# RNG_entropy.net
KiCad netlist of a schematic drawn in Altium Designer
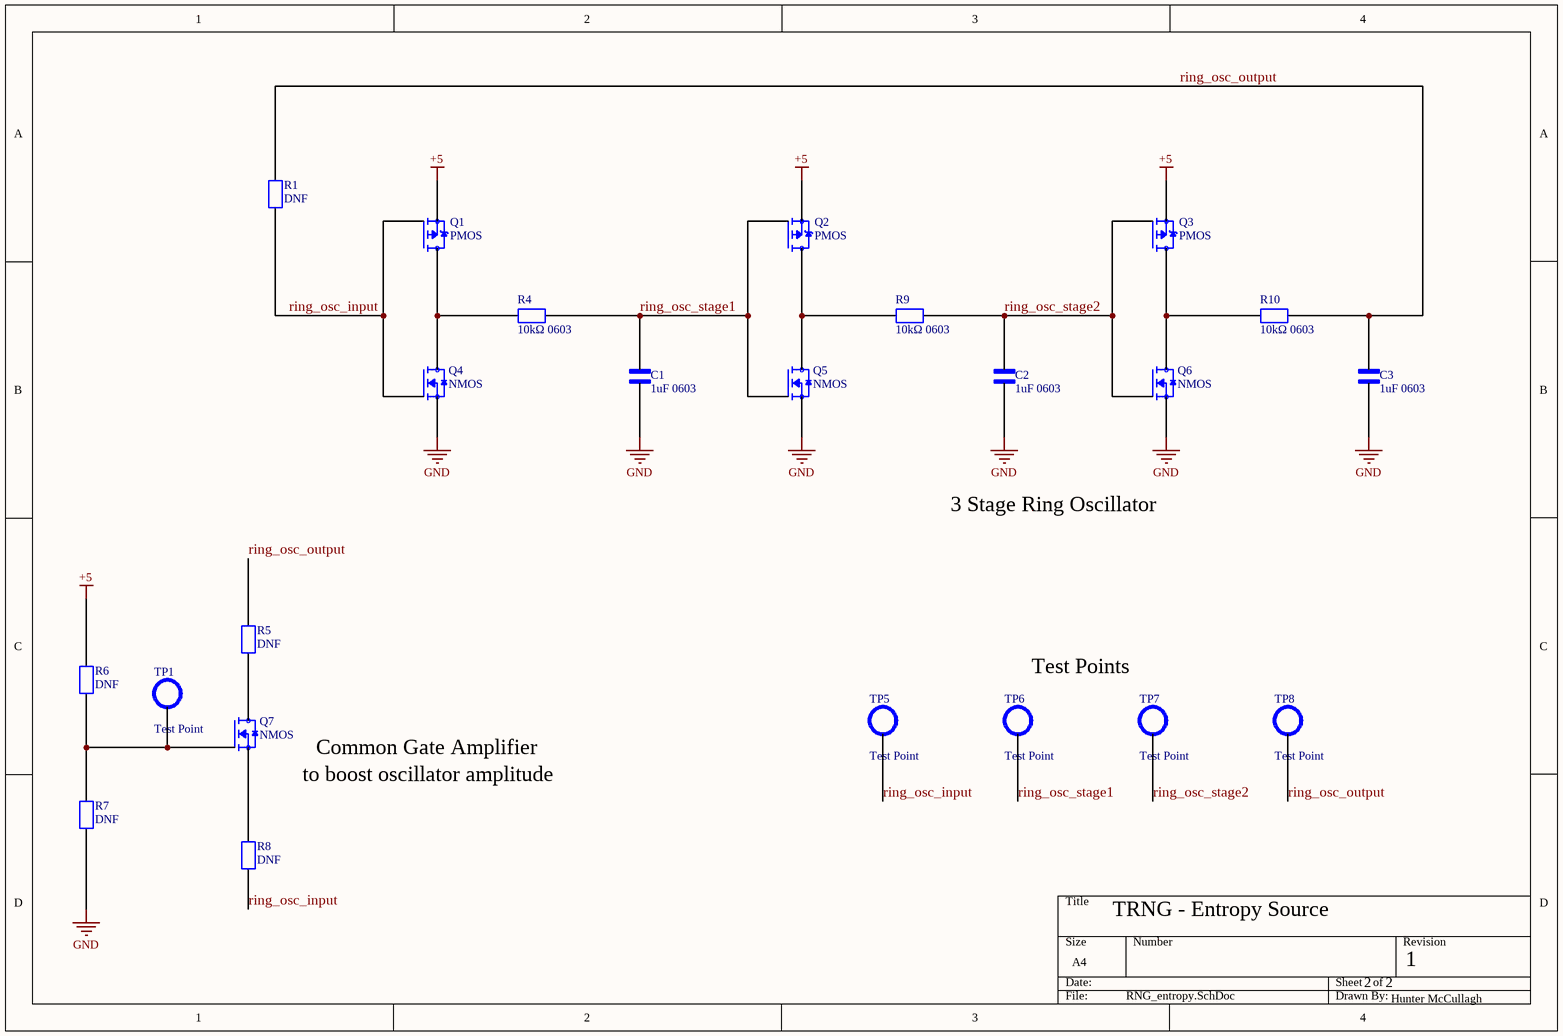
[diagram p0: RNG_entropy.SchDoc]

(export (version "E")
  (design (tool "Eeschema 10.0.6"))
  (components
    (comp (ref "C1")
      (value "1uF 0603")
      (footprint "0603 PACKAGE")
      (libsource (lib "RNG_schematic_lib") (part "0603_Capacitor"))
    )
    (comp (ref "C2")
      (value "1uF 0603")
      (footprint "0603 PACKAGE")
      (libsource (lib "RNG_schematic_lib") (part "0603_Capacitor"))
    )
    (comp (ref "C3")
      (value "1uF 0603")
      (footprint "0603 PACKAGE")
      (libsource (lib "RNG_schematic_lib") (part "0603_Capacitor"))
    )
    (comp (ref "Q1")
      (value "PMOS")
      (footprint "SOT23-3")
      (description "P-Channel 30 V 4A (Ta) 1.4W (Ta) Surface Mount SOT-23-3")
      (fields (field (name "MF") "Alpha & Omega Semiconductor") (field (name "MP") "AO3401A"))
      (libsource (lib "RNG_schematic_lib") (part "AO3401A"))
    )
    (comp (ref "Q2")
      (value "PMOS")
      (footprint "SOT23-3")
      (description "P-Channel 30 V 4A (Ta) 1.4W (Ta) Surface Mount SOT-23-3")
      (fields (field (name "MF") "Alpha & Omega Semiconductor") (field (name "MP") "AO3401A"))
      (libsource (lib "RNG_schematic_lib") (part "AO3401A"))
    )
    (comp (ref "Q3")
      (value "PMOS")
      (footprint "SOT23-3")
      (description "P-Channel 30 V 4A (Ta) 1.4W (Ta) Surface Mount SOT-23-3")
      (fields (field (name "MF") "Alpha & Omega Semiconductor") (field (name "MP") "AO3401A"))
      (libsource (lib "RNG_schematic_lib") (part "AO3401A"))
    )
    (comp (ref "Q4")
      (value "NMOS")
      (footprint "SOT23-3")
      (description "N-Channel 30 V 5.7A (Ta) 1.4W (Ta) Surface Mount SOT-23-3")
      (fields (field (name "MF") "Alpha & Omega Semiconductor") (field (name "MP") "AO3400A"))
      (libsource (lib "RNG_schematic_lib") (part "AO3400A"))
    )
    (comp (ref "Q5")
      (value "NMOS")
      (footprint "SOT23-3")
      (description "N-Channel 30 V 5.7A (Ta) 1.4W (Ta) Surface Mount SOT-23-3")
      (fields (field (name "MF") "Alpha & Omega Semiconductor") (field (name "MP") "AO3400A"))
      (libsource (lib "RNG_schematic_lib") (part "AO3400A"))
    )
    (comp (ref "Q6")
      (value "NMOS")
      (footprint "SOT23-3")
      (description "N-Channel 30 V 5.7A (Ta) 1.4W (Ta) Surface Mount SOT-23-3")
      (fields (field (name "MF") "Alpha & Omega Semiconductor") (field (name "MP") "AO3400A"))
      (libsource (lib "RNG_schematic_lib") (part "AO3400A"))
    )
    (comp (ref "Q7")
      (value "NMOS")
      (footprint "SOT23-3")
      (description "N-Channel 30 V 5.7A (Ta) 1.4W (Ta) Surface Mount SOT-23-3")
      (fields (field (name "MF") "Alpha & Omega Semiconductor") (field (name "MP") "AO3400A"))
      (libsource (lib "RNG_schematic_lib") (part "AO3400A"))
    )
    (comp (ref "R1")
      (value "DNF")
      (footprint "0402 PACKAGE")
      (libsource (lib "RNG_schematic_lib") (part "0402_Resistor"))
    )
    (comp (ref "R4")
      (value "10kΩ 0603")
      (footprint "0603 PACKAGE")
      (libsource (lib "RNG_schematic_lib") (part "0603_Resistor"))
    )
    (comp (ref "R5")
      (value "DNF")
      (footprint "0402 PACKAGE")
      (libsource (lib "RNG_schematic_lib") (part "0402_Resistor"))
    )
    (comp (ref "R6")
      (value "DNF")
      (footprint "0603 PACKAGE")
      (libsource (lib "RNG_schematic_lib") (part "0603_Resistor"))
    )
    (comp (ref "R7")
      (value "DNF")
      (footprint "0603 PACKAGE")
      (libsource (lib "RNG_schematic_lib") (part "0603_Resistor"))
    )
    (comp (ref "R8")
      (value "DNF")
      (footprint "0402 PACKAGE")
      (libsource (lib "RNG_schematic_lib") (part "0402_Resistor"))
    )
    (comp (ref "R9")
      (value "10kΩ 0603")
      (footprint "0603 PACKAGE")
      (libsource (lib "RNG_schematic_lib") (part "0603_Resistor"))
    )
    (comp (ref "R10")
      (value "10kΩ 0603")
      (footprint "0603 PACKAGE")
      (libsource (lib "RNG_schematic_lib") (part "0603_Resistor"))
    )
    (comp (ref "TP1")
      (value "Test Point")
      (footprint "Test Point")
      (libsource (lib "RNG_schematic_lib") (part "Test Point"))
    )
    (comp (ref "TP5")
      (value "Test Point")
      (footprint "Test Point")
      (libsource (lib "RNG_schematic_lib") (part "Test Point"))
    )
    (comp (ref "TP6")
      (value "Test Point")
      (footprint "Test Point")
      (libsource (lib "RNG_schematic_lib") (part "Test Point"))
    )
    (comp (ref "TP7")
      (value "Test Point")
      (footprint "Test Point")
      (libsource (lib "RNG_schematic_lib") (part "Test Point"))
    )
    (comp (ref "TP8")
      (value "Test Point")
      (footprint "Test Point")
      (libsource (lib "RNG_schematic_lib") (part "Test Point"))
    )
  )
  (nets
    (net (code "1") (name "+5") (class "Default")
      (node (ref "Q1") (pin "2") (pinfunction "S_2") (pintype "passive"))
      (node (ref "Q2") (pin "2") (pinfunction "S_2") (pintype "passive"))
      (node (ref "Q3") (pin "2") (pinfunction "S_2") (pintype "passive"))
      (node (ref "R6") (pin "2") (pinfunction "2_2") (pintype "passive"))
    )
    (net (code "2") (name "/ring_osc_input") (class "Default")
      (node (ref "Q1") (pin "1") (pinfunction "G_1") (pintype "passive"))
      (node (ref "Q4") (pin "1") (pinfunction "G_1") (pintype "passive"))
      (node (ref "R1") (pin "1") (pinfunction "1_1") (pintype "passive"))
      (node (ref "R8") (pin "1") (pinfunction "1_1") (pintype "passive"))
      (node (ref "TP5") (pin "1") (pinfunction "1_1") (pintype "passive"))
    )
    (net (code "3") (name "/ring_osc_output") (class "Default")
      (node (ref "C3") (pin "2") (pinfunction "2_2") (pintype "passive"))
      (node (ref "R1") (pin "2") (pinfunction "2_2") (pintype "passive"))
      (node (ref "R10") (pin "2") (pinfunction "2_2") (pintype "passive"))
      (node (ref "R5") (pin "2") (pinfunction "2_2") (pintype "passive"))
      (node (ref "TP8") (pin "1") (pinfunction "1_1") (pintype "passive"))
    )
    (net (code "4") (name "/ring_osc_stage1") (class "Default")
      (node (ref "C1") (pin "2") (pinfunction "2_2") (pintype "passive"))
      (node (ref "Q2") (pin "1") (pinfunction "G_1") (pintype "passive"))
      (node (ref "Q5") (pin "1") (pinfunction "G_1") (pintype "passive"))
      (node (ref "R4") (pin "2") (pinfunction "2_2") (pintype "passive"))
      (node (ref "TP6") (pin "1") (pinfunction "1_1") (pintype "passive"))
    )
    (net (code "5") (name "/ring_osc_stage2") (class "Default")
      (node (ref "C2") (pin "2") (pinfunction "2_2") (pintype "passive"))
      (node (ref "Q3") (pin "1") (pinfunction "G_1") (pintype "passive"))
      (node (ref "Q6") (pin "1") (pinfunction "G_1") (pintype "passive"))
      (node (ref "R9") (pin "2") (pinfunction "2_2") (pintype "passive"))
      (node (ref "TP7") (pin "1") (pinfunction "1_1") (pintype "passive"))
    )
    (net (code "6") (name "GND") (class "Default")
      (node (ref "C1") (pin "1") (pinfunction "1_1") (pintype "passive"))
      (node (ref "C2") (pin "1") (pinfunction "1_1") (pintype "passive"))
      (node (ref "C3") (pin "1") (pinfunction "1_1") (pintype "passive"))
      (node (ref "Q4") (pin "2") (pinfunction "S_2") (pintype "passive"))
      (node (ref "Q5") (pin "2") (pinfunction "S_2") (pintype "passive"))
      (node (ref "Q6") (pin "2") (pinfunction "S_2") (pintype "passive"))
      (node (ref "R7") (pin "1") (pinfunction "1_1") (pintype "passive"))
    )
    (net (code "7") (name "Net-(Q1-D)") (class "Default")
      (node (ref "Q1") (pin "3") (pinfunction "D_3") (pintype "passive"))
      (node (ref "Q4") (pin "3") (pinfunction "D_3") (pintype "passive"))
      (node (ref "R4") (pin "1") (pinfunction "1_1") (pintype "passive"))
    )
    (net (code "8") (name "Net-(Q2-D)") (class "Default")
      (node (ref "Q2") (pin "3") (pinfunction "D_3") (pintype "passive"))
      (node (ref "Q5") (pin "3") (pinfunction "D_3") (pintype "passive"))
      (node (ref "R9") (pin "1") (pinfunction "1_1") (pintype "passive"))
    )
    (net (code "9") (name "Net-(Q3-D)") (class "Default")
      (node (ref "Q3") (pin "3") (pinfunction "D_3") (pintype "passive"))
      (node (ref "Q6") (pin "3") (pinfunction "D_3") (pintype "passive"))
      (node (ref "R10") (pin "1") (pinfunction "1_1") (pintype "passive"))
    )
    (net (code "10") (name "Net-(Q7-D)") (class "Default")
      (node (ref "Q7") (pin "3") (pinfunction "D_3") (pintype "passive"))
      (node (ref "R5") (pin "1") (pinfunction "1_1") (pintype "passive"))
    )
    (net (code "11") (name "Net-(Q7-G)") (class "Default")
      (node (ref "Q7") (pin "1") (pinfunction "G_1") (pintype "passive"))
      (node (ref "R6") (pin "1") (pinfunction "1_1") (pintype "passive"))
      (node (ref "R7") (pin "2") (pinfunction "2_2") (pintype "passive"))
      (node (ref "TP1") (pin "1") (pinfunction "1_1") (pintype "passive"))
    )
    (net (code "12") (name "Net-(Q7-S)") (class "Default")
      (node (ref "Q7") (pin "2") (pinfunction "S_2") (pintype "passive"))
      (node (ref "R8") (pin "2") (pinfunction "2_2") (pintype "passive"))
    )
  )
)
